# 1_P1.net
KiCad netlist of a schematic drawn in Altium Designer
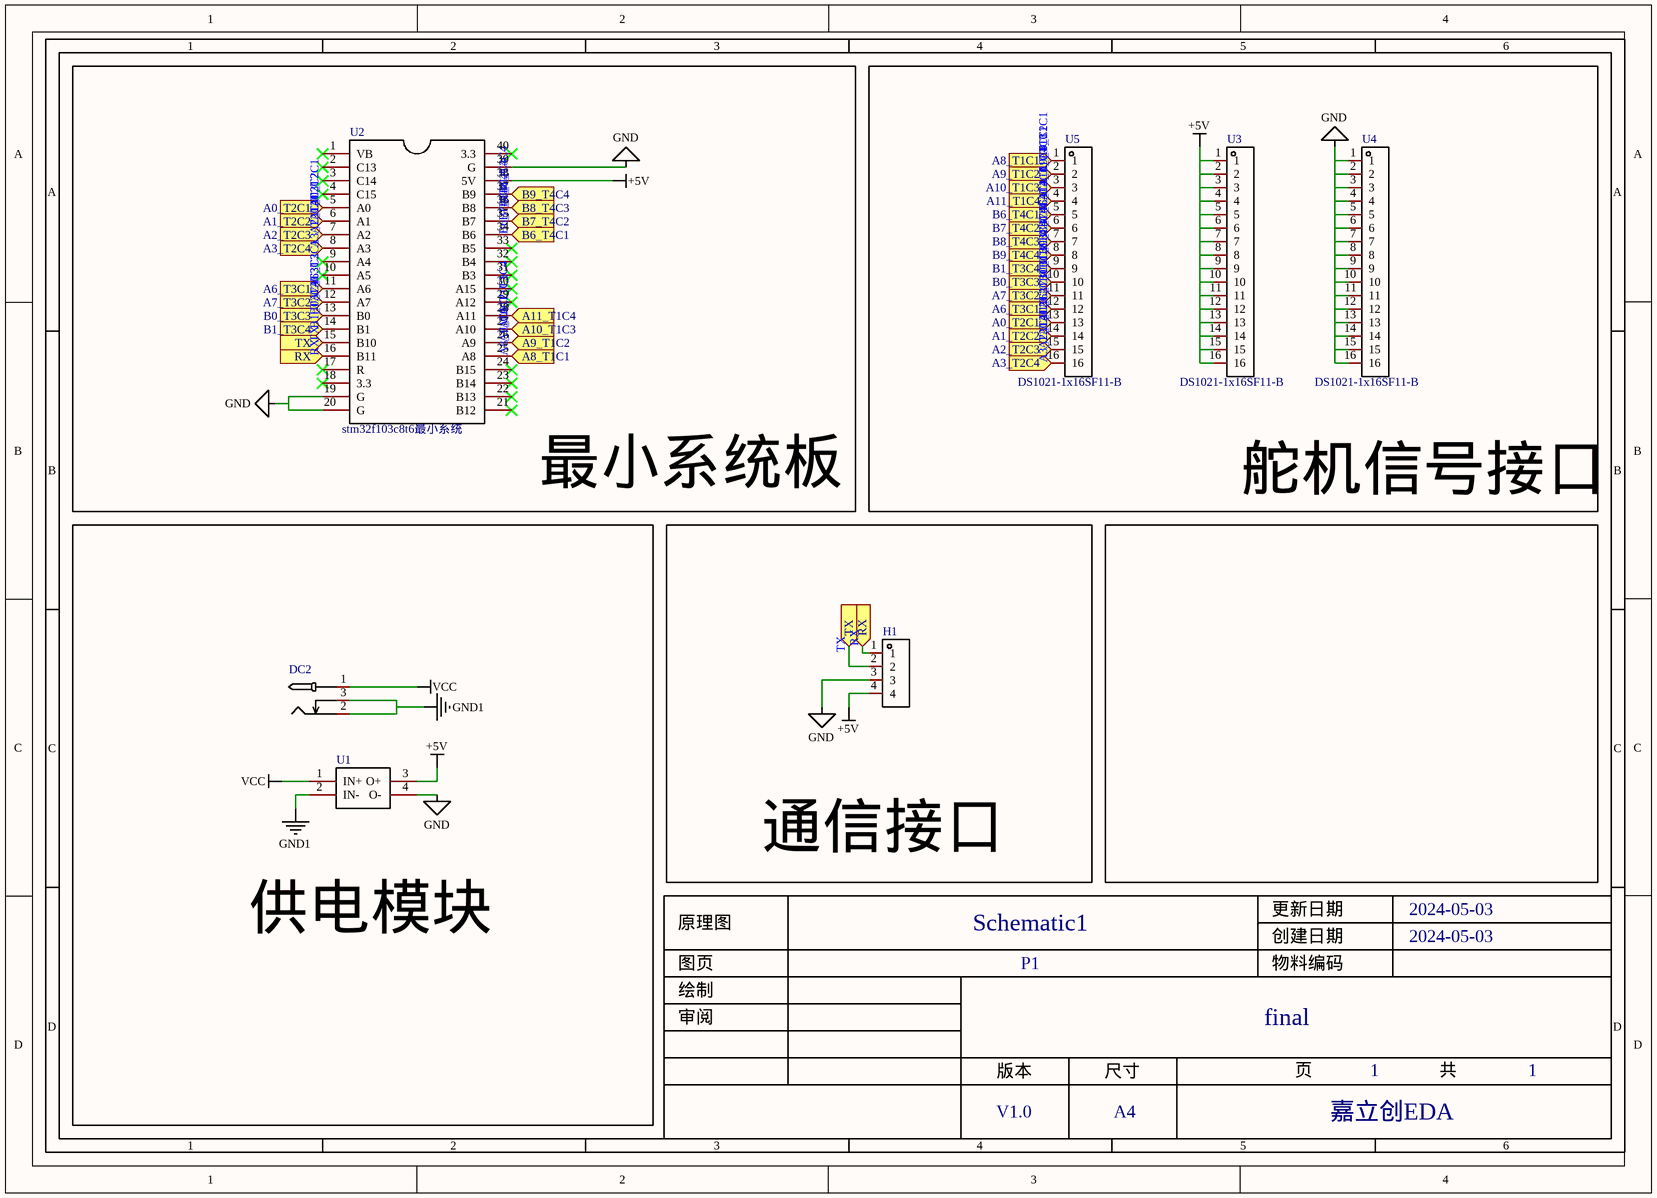
[diagram p0: 1_P1.schdoc]

(export (version "E")
  (design (tool "Eeschema 10.0.6"))
  (components
    (comp (ref "DC2") (value "DC-005_2.5") (libsource (lib "altium-import") (part "root_0_DC-005_2.5_")))
    (comp (ref "H1")
      (value "HDR-F_2.54_1x4P")
      (fields (field (name "MANUFACTURER") "BOOMELE(博穆精密)") (field (name "MANUFACTURER PART") "2.54-1*4P母"))
      (libsource (lib "altium-import") (part "root_0_HDR-F_2.54_1x4P_"))
    )
    (comp (ref "U1") (value "LM2596") (libsource (lib "altium-import") (part "root_0_LM2596_")))
    (comp (ref "U2")
      (value "stm32f103c8t6最小系统")
      (fields (field (name "NAME") "stm32f103c8t6最小系统"))
      (libsource (lib "altium-import") (part "root_0_stm32f103c8t6最小系统_"))
    )
    (comp (ref "U3")
      (value "DS1021-1x16SF11-B")
      (description "插针结构:1x16P;间距:2.54mm;安装类型:直插;排数:单排;总PIN位数:16P;")
      (fields (field (name "NAME") "DS1021-1x16SF11-B") (field (name "MANUFACTURER") "CONNFLY"))
      (libsource (lib "altium-import") (part "root_0_DS1021-1x16SF11-B_"))
    )
    (comp (ref "U4")
      (value "DS1021-1x16SF11-B")
      (description "插针结构:1x16P;间距:2.54mm;安装类型:直插;排数:单排;总PIN位数:16P;")
      (fields (field (name "NAME") "DS1021-1x16SF11-B") (field (name "MANUFACTURER") "CONNFLY"))
      (libsource (lib "altium-import") (part "root_0_DS1021-1x16SF11-B_"))
    )
    (comp (ref "U5")
      (value "DS1021-1x16SF11-B")
      (description "插针结构:1x16P;间距:2.54mm;安装类型:直插;排数:单排;总PIN位数:16P;")
      (fields (field (name "NAME") "DS1021-1x16SF11-B") (field (name "MANUFACTURER") "CONNFLY"))
      (libsource (lib "altium-import") (part "root_0_DS1021-1x16SF11-B_"))
    )
  )
  (nets
    (net (code "1") (name "+5V") (class "Default")
      (node (ref "H1") (pin "4") (pinfunction "4_4") (pintype "passive"))
      (node (ref "U1") (pin "3") (pinfunction "O+_3") (pintype "passive"))
      (node (ref "U2") (pin "38") (pinfunction "5V_38") (pintype "passive"))
      (node (ref "U3") (pin "1") (pinfunction "1_1") (pintype "passive"))
      (node (ref "U3") (pin "10") (pinfunction "10_10") (pintype "passive"))
      (node (ref "U3") (pin "11") (pinfunction "11_11") (pintype "passive"))
      (node (ref "U3") (pin "12") (pinfunction "12_12") (pintype "passive"))
      (node (ref "U3") (pin "13") (pinfunction "13_13") (pintype "passive"))
      (node (ref "U3") (pin "14") (pinfunction "14_14") (pintype "passive"))
      (node (ref "U3") (pin "15") (pinfunction "15_15") (pintype "passive"))
      (node (ref "U3") (pin "16") (pinfunction "16_16") (pintype "passive"))
      (node (ref "U3") (pin "2") (pinfunction "2_2") (pintype "passive"))
      (node (ref "U3") (pin "3") (pinfunction "3_3") (pintype "passive"))
      (node (ref "U3") (pin "4") (pinfunction "4_4") (pintype "passive"))
      (node (ref "U3") (pin "5") (pinfunction "5_5") (pintype "passive"))
      (node (ref "U3") (pin "6") (pinfunction "6_6") (pintype "passive"))
      (node (ref "U3") (pin "7") (pinfunction "7_7") (pintype "passive"))
      (node (ref "U3") (pin "8") (pinfunction "8_8") (pintype "passive"))
      (node (ref "U3") (pin "9") (pinfunction "9_9") (pintype "passive"))
    )
    (net (code "2") (name "/A0_T2C1") (class "Default")
      (node (ref "U2") (pin "5") (pinfunction "A0_5") (pintype "passive"))
      (node (ref "U5") (pin "13") (pinfunction "13_13") (pintype "passive"))
    )
    (net (code "3") (name "/A1_T2C2") (class "Default")
      (node (ref "U2") (pin "6") (pinfunction "A1_6") (pintype "passive"))
      (node (ref "U5") (pin "14") (pinfunction "14_14") (pintype "passive"))
    )
    (net (code "4") (name "/A2_T2C3") (class "Default")
      (node (ref "U2") (pin "7") (pinfunction "A2_7") (pintype "passive"))
      (node (ref "U5") (pin "15") (pinfunction "15_15") (pintype "passive"))
    )
    (net (code "5") (name "/A3_T2C4") (class "Default")
      (node (ref "U2") (pin "8") (pinfunction "A3_8") (pintype "passive"))
      (node (ref "U5") (pin "16") (pinfunction "16_16") (pintype "passive"))
    )
    (net (code "6") (name "/A6_T3C1") (class "Default")
      (node (ref "U2") (pin "11") (pinfunction "A6_11") (pintype "passive"))
      (node (ref "U5") (pin "12") (pinfunction "12_12") (pintype "passive"))
    )
    (net (code "7") (name "/A7_T3C2") (class "Default")
      (node (ref "U2") (pin "12") (pinfunction "A7_12") (pintype "passive"))
      (node (ref "U5") (pin "11") (pinfunction "11_11") (pintype "passive"))
    )
    (net (code "8") (name "/A8_T1C1") (class "Default")
      (node (ref "U2") (pin "25") (pinfunction "A8_25") (pintype "passive"))
      (node (ref "U5") (pin "1") (pinfunction "1_1") (pintype "passive"))
    )
    (net (code "9") (name "/A9_T1C2") (class "Default")
      (node (ref "U2") (pin "26") (pinfunction "A9_26") (pintype "passive"))
      (node (ref "U5") (pin "2") (pinfunction "2_2") (pintype "passive"))
    )
    (net (code "10") (name "/A10_T1C3") (class "Default")
      (node (ref "U2") (pin "27") (pinfunction "A10_27") (pintype "passive"))
      (node (ref "U5") (pin "3") (pinfunction "3_3") (pintype "passive"))
    )
    (net (code "11") (name "/A11_T1C4") (class "Default")
      (node (ref "U2") (pin "28") (pinfunction "A11_28") (pintype "passive"))
      (node (ref "U5") (pin "4") (pinfunction "4_4") (pintype "passive"))
    )
    (net (code "12") (name "/B0_T3C3") (class "Default")
      (node (ref "U2") (pin "13") (pinfunction "B0_13") (pintype "passive"))
      (node (ref "U5") (pin "10") (pinfunction "10_10") (pintype "passive"))
    )
    (net (code "13") (name "/B1_T3C4") (class "Default")
      (node (ref "U2") (pin "14") (pinfunction "B1_14") (pintype "passive"))
      (node (ref "U5") (pin "9") (pinfunction "9_9") (pintype "passive"))
    )
    (net (code "14") (name "/B6_T4C1") (class "Default")
      (node (ref "U2") (pin "34") (pinfunction "B6_34") (pintype "passive"))
      (node (ref "U5") (pin "5") (pinfunction "5_5") (pintype "passive"))
    )
    (net (code "15") (name "/B7_T4C2") (class "Default")
      (node (ref "U2") (pin "35") (pinfunction "B7_35") (pintype "passive"))
      (node (ref "U5") (pin "6") (pinfunction "6_6") (pintype "passive"))
    )
    (net (code "16") (name "/B8_T4C3") (class "Default")
      (node (ref "U2") (pin "36") (pinfunction "B8_36") (pintype "passive"))
      (node (ref "U5") (pin "7") (pinfunction "7_7") (pintype "passive"))
    )
    (net (code "17") (name "/B9_T4C4") (class "Default")
      (node (ref "U2") (pin "37") (pinfunction "B9_37") (pintype "passive"))
      (node (ref "U5") (pin "8") (pinfunction "8_8") (pintype "passive"))
    )
    (net (code "18") (name "/RX") (class "Default")
      (node (ref "H1") (pin "1") (pinfunction "1_1") (pintype "passive"))
      (node (ref "U2") (pin "16") (pinfunction "B11_16") (pintype "passive"))
    )
    (net (code "19") (name "/TX") (class "Default")
      (node (ref "H1") (pin "2") (pinfunction "2_2") (pintype "passive"))
      (node (ref "U2") (pin "15") (pinfunction "B10_15") (pintype "passive"))
    )
    (net (code "20") (name "GND") (class "Default")
      (node (ref "H1") (pin "3") (pinfunction "3_3") (pintype "passive"))
      (node (ref "U1") (pin "4") (pinfunction "O-_4") (pintype "passive"))
      (node (ref "U2") (pin "19") (pinfunction "G_19") (pintype "passive"))
      (node (ref "U2") (pin "20") (pinfunction "G_20") (pintype "passive"))
      (node (ref "U2") (pin "39") (pinfunction "G_39") (pintype "passive"))
      (node (ref "U4") (pin "1") (pinfunction "1_1") (pintype "passive"))
      (node (ref "U4") (pin "10") (pinfunction "10_10") (pintype "passive"))
      (node (ref "U4") (pin "11") (pinfunction "11_11") (pintype "passive"))
      (node (ref "U4") (pin "12") (pinfunction "12_12") (pintype "passive"))
      (node (ref "U4") (pin "13") (pinfunction "13_13") (pintype "passive"))
      (node (ref "U4") (pin "14") (pinfunction "14_14") (pintype "passive"))
      (node (ref "U4") (pin "15") (pinfunction "15_15") (pintype "passive"))
      (node (ref "U4") (pin "16") (pinfunction "16_16") (pintype "passive"))
      (node (ref "U4") (pin "2") (pinfunction "2_2") (pintype "passive"))
      (node (ref "U4") (pin "3") (pinfunction "3_3") (pintype "passive"))
      (node (ref "U4") (pin "4") (pinfunction "4_4") (pintype "passive"))
      (node (ref "U4") (pin "5") (pinfunction "5_5") (pintype "passive"))
      (node (ref "U4") (pin "6") (pinfunction "6_6") (pintype "passive"))
      (node (ref "U4") (pin "7") (pinfunction "7_7") (pintype "passive"))
      (node (ref "U4") (pin "8") (pinfunction "8_8") (pintype "passive"))
      (node (ref "U4") (pin "9") (pinfunction "9_9") (pintype "passive"))
    )
    (net (code "21") (name "GND1") (class "Default")
      (node (ref "DC2") (pin "2") (pinfunction "2_2") (pintype "passive"))
      (node (ref "DC2") (pin "3") (pinfunction "3_3") (pintype "passive"))
      (node (ref "U1") (pin "2") (pinfunction "IN-_2") (pintype "passive"))
    )
    (net (code "22") (name "VCC") (class "Default")
      (node (ref "DC2") (pin "1") (pinfunction "4_1") (pintype "passive"))
      (node (ref "U1") (pin "1") (pinfunction "IN+_1") (pintype "passive"))
    )
    (net (code "23") (name "unconnected-(U2-3.3-Pad18)") (class "Default")
      (node (ref "U2") (pin "18") (pinfunction "3.3_18") (pintype "passive+no_connect"))
    )
    (net (code "24") (name "unconnected-(U2-3.3-Pad40)") (class "Default")
      (node (ref "U2") (pin "40") (pinfunction "3.3_40") (pintype "passive+no_connect"))
    )
    (net (code "25") (name "unconnected-(U2-A4-Pad9)") (class "Default")
      (node (ref "U2") (pin "9") (pinfunction "A4_9") (pintype "passive+no_connect"))
    )
    (net (code "26") (name "unconnected-(U2-A5-Pad10)") (class "Default")
      (node (ref "U2") (pin "10") (pinfunction "A5_10") (pintype "passive+no_connect"))
    )
    (net (code "27") (name "unconnected-(U2-A12-Pad29)") (class "Default")
      (node (ref "U2") (pin "29") (pinfunction "A12_29") (pintype "passive+no_connect"))
    )
    (net (code "28") (name "unconnected-(U2-A15-Pad30)") (class "Default")
      (node (ref "U2") (pin "30") (pinfunction "A15_30") (pintype "passive+no_connect"))
    )
    (net (code "29") (name "unconnected-(U2-B3-Pad31)") (class "Default")
      (node (ref "U2") (pin "31") (pinfunction "B3_31") (pintype "passive+no_connect"))
    )
    (net (code "30") (name "unconnected-(U2-B4-Pad32)") (class "Default")
      (node (ref "U2") (pin "32") (pinfunction "B4_32") (pintype "passive+no_connect"))
    )
    (net (code "31") (name "unconnected-(U2-B5-Pad33)") (class "Default")
      (node (ref "U2") (pin "33") (pinfunction "B5_33") (pintype "passive+no_connect"))
    )
    (net (code "32") (name "unconnected-(U2-B12-Pad21)") (class "Default")
      (node (ref "U2") (pin "21") (pinfunction "B12_21") (pintype "passive+no_connect"))
    )
    (net (code "33") (name "unconnected-(U2-B13-Pad22)") (class "Default")
      (node (ref "U2") (pin "22") (pinfunction "B13_22") (pintype "passive+no_connect"))
    )
    (net (code "34") (name "unconnected-(U2-B14-Pad23)") (class "Default")
      (node (ref "U2") (pin "23") (pinfunction "B14_23") (pintype "passive+no_connect"))
    )
    (net (code "35") (name "unconnected-(U2-B15-Pad24)") (class "Default")
      (node (ref "U2") (pin "24") (pinfunction "B15_24") (pintype "passive+no_connect"))
    )
    (net (code "36") (name "unconnected-(U2-C13-Pad2)") (class "Default")
      (node (ref "U2") (pin "2") (pinfunction "C13_2") (pintype "passive+no_connect"))
    )
    (net (code "37") (name "unconnected-(U2-C14-Pad3)") (class "Default")
      (node (ref "U2") (pin "3") (pinfunction "C14_3") (pintype "passive+no_connect"))
    )
    (net (code "38") (name "unconnected-(U2-C15-Pad4)") (class "Default")
      (node (ref "U2") (pin "4") (pinfunction "C15_4") (pintype "passive+no_connect"))
    )
    (net (code "39") (name "unconnected-(U2-R-Pad17)") (class "Default")
      (node (ref "U2") (pin "17") (pinfunction "R_17") (pintype "passive+no_connect"))
    )
    (net (code "40") (name "unconnected-(U2-VB-Pad1)") (class "Default")
      (node (ref "U2") (pin "1") (pinfunction "VB_1") (pintype "passive+no_connect"))
    )
  )
)
